# motorcontrol.net
KiCad netlist of a schematic drawn in EAGLE
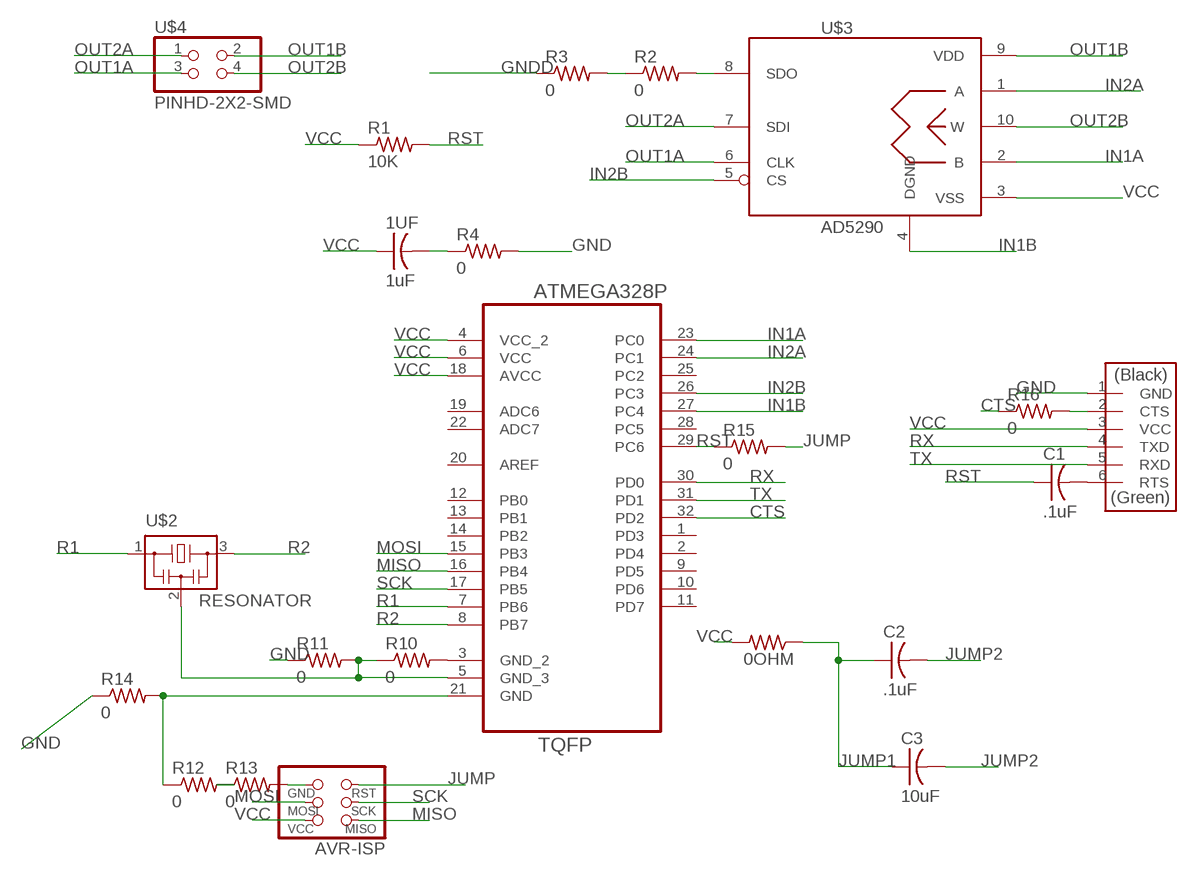
[diagram p0: schematic, sheet 1]

(export (version "E")
  (design (tool "Eeschema 10.0.6"))
  (components
    (comp (ref "0OHM")
      (value "RES-US1206FAB")
      (footprint "eagle-import:R1206FAB")
      (libsource (lib "eagle-import") (part "RES-US1206FAB"))
    )
    (comp (ref "1UF")
      (value "1uF")
      (footprint "eagle-import:C1206FAB")
      (libsource (lib "eagle-import") (part "CAP-US1206FAB"))
    )
    (comp (ref "AVR-ISP")
      (value "AVRISPSMD")
      (footprint "eagle-import:2X03SMD")
      (libsource (lib "eagle-import") (part "AVRISPSMD"))
    )
    (comp (ref "C1")
      (value ".1uF")
      (footprint "eagle-import:C1206FAB")
      (libsource (lib "eagle-import") (part "CAP-US1206FAB"))
    )
    (comp (ref "C2")
      (value ".1uF")
      (footprint "eagle-import:C1206FAB")
      (libsource (lib "eagle-import") (part "CAP-US1206FAB"))
    )
    (comp (ref "C3")
      (value "10uF")
      (footprint "eagle-import:C1206FAB")
      (libsource (lib "eagle-import") (part "CAP-US1206FAB"))
    )
    (comp (ref "R1")
      (value "10K")
      (footprint "eagle-import:R1206FAB")
      (libsource (lib "eagle-import") (part "RES-US1206FAB"))
    )
    (comp (ref "R2")
      (value "0")
      (footprint "eagle-import:R1206FAB")
      (libsource (lib "eagle-import") (part "RES-US1206FAB"))
    )
    (comp (ref "R3")
      (value "0")
      (footprint "eagle-import:R1206FAB")
      (libsource (lib "eagle-import") (part "RES-US1206FAB"))
    )
    (comp (ref "R4")
      (value "0")
      (footprint "eagle-import:R1206FAB")
      (libsource (lib "eagle-import") (part "RES-US1206FAB"))
    )
    (comp (ref "R10")
      (value "0")
      (footprint "eagle-import:R1206FAB")
      (libsource (lib "eagle-import") (part "RES-US1206FAB"))
    )
    (comp (ref "R11")
      (value "0")
      (footprint "eagle-import:R1206FAB")
      (libsource (lib "eagle-import") (part "RES-US1206FAB"))
    )
    (comp (ref "R12")
      (value "0")
      (footprint "eagle-import:R1206")
      (libsource (lib "eagle-import") (part "RES-US1206"))
    )
    (comp (ref "R13")
      (value "0")
      (footprint "eagle-import:R1206")
      (libsource (lib "eagle-import") (part "RES-US1206"))
    )
    (comp (ref "R14")
      (value "0")
      (footprint "eagle-import:R1206FAB")
      (libsource (lib "eagle-import") (part "RES-US1206FAB"))
    )
    (comp (ref "R15")
      (value "0")
      (footprint "eagle-import:R1206FAB")
      (libsource (lib "eagle-import") (part "RES-US1206FAB"))
    )
    (comp (ref "R16")
      (value "0")
      (footprint "eagle-import:R1206FAB")
      (libsource (lib "eagle-import") (part "RES-US1206FAB"))
    )
    (comp (ref "U$1")
      (value "FTDI-SMD-HEADER")
      (footprint "eagle-import:1X06SMD")
      (libsource (lib "eagle-import") (part "FTDI-SMD-HEADER"))
    )
    (comp (ref "U$2")
      (value "RESONATOR")
      (footprint "eagle-import:EFOBM")
      (libsource (lib "eagle-import") (part "RESONATOR"))
    )
    (comp (ref "U$3")
      (value "AD5290")
      (footprint "eagle-import:MSOP_10")
      (libsource (lib "eagle-import") (part "AD5290"))
    )
    (comp (ref "U$4")
      (value "PINHD-2X2-SMD")
      (footprint "eagle-import:2X02SMD")
      (libsource (lib "eagle-import") (part "PINHD-2X2-SMD"))
    )
    (comp (ref "U1")
      (value "ATMEGA328P-AU")
      (footprint "eagle-import:QFP80P900X900X120-32N")
      (libsource (lib "eagle-import") (part "ATMEGA328P-AU"))
    )
  )
  (nets
    (net (code "1") (name "/CTS") (class "Default")
      (node (ref "R16") (pin "1") (pinfunction "1_1") (pintype "passive"))
      (node (ref "U1") (pin "32") (pinfunction "PD2_32") (pintype "bidirectional"))
    )
    (net (code "2") (name "/GND") (class "Default")
      (node (ref "R11") (pin "1") (pinfunction "1_1") (pintype "passive"))
      (node (ref "R14") (pin "1") (pinfunction "1_1") (pintype "passive"))
      (node (ref "R4") (pin "2") (pinfunction "2_2") (pintype "passive"))
      (node (ref "U$1") (pin "1") (pinfunction "GND_1") (pintype "bidirectional"))
    )
    (net (code "3") (name "/GNDD") (class "Default")
      (node (ref "R12") (pin "1") (pinfunction "1_1") (pintype "passive"))
      (node (ref "R14") (pin "2") (pinfunction "2_2") (pintype "passive"))
      (node (ref "R3") (pin "1") (pinfunction "1_1") (pintype "passive"))
      (node (ref "U1") (pin "21") (pinfunction "GND_21") (pintype "passive"))
    )
    (net (code "4") (name "/IN1A") (class "Default")
      (node (ref "U$3") (pin "2") (pinfunction "B_2") (pintype "bidirectional"))
      (node (ref "U1") (pin "23") (pinfunction "PC0_23") (pintype "bidirectional"))
    )
    (net (code "5") (name "/IN1B") (class "Default")
      (node (ref "U$3") (pin "4") (pinfunction "DGND_4") (pintype "bidirectional"))
      (node (ref "U1") (pin "27") (pinfunction "PC4_27") (pintype "bidirectional"))
    )
    (net (code "6") (name "/IN2A") (class "Default")
      (node (ref "U$3") (pin "1") (pinfunction "A_1") (pintype "bidirectional"))
      (node (ref "U1") (pin "24") (pinfunction "PC1_24") (pintype "bidirectional"))
    )
    (net (code "7") (name "/IN2B") (class "Default")
      (node (ref "U$3") (pin "5") (pinfunction "CS_5") (pintype "input"))
      (node (ref "U1") (pin "26") (pinfunction "PC3_26") (pintype "bidirectional"))
    )
    (net (code "8") (name "/JUMP") (class "Default")
      (node (ref "AVR-ISP") (pin "5") (pinfunction "RST_5") (pintype "passive"))
      (node (ref "R15") (pin "2") (pinfunction "2_2") (pintype "passive"))
    )
    (net (code "9") (name "/JUMP1") (class "Default")
      (node (ref "0OHM") (pin "1") (pinfunction "1_1") (pintype "passive"))
      (node (ref "C2") (pin "1") (pinfunction "1_1") (pintype "passive"))
      (node (ref "C3") (pin "1") (pinfunction "1_1") (pintype "passive"))
    )
    (net (code "10") (name "/JUMP2") (class "Default")
      (node (ref "C2") (pin "2") (pinfunction "2_2") (pintype "passive"))
      (node (ref "C3") (pin "2") (pinfunction "2_2") (pintype "passive"))
      (node (ref "R2") (pin "2") (pinfunction "2_2") (pintype "passive"))
      (node (ref "U$3") (pin "8") (pinfunction "SDO_8") (pintype "bidirectional"))
    )
    (net (code "11") (name "/MISO") (class "Default")
      (node (ref "AVR-ISP") (pin "1") (pinfunction "MISO_1") (pintype "passive"))
      (node (ref "U1") (pin "16") (pinfunction "PB4_16") (pintype "bidirectional"))
    )
    (net (code "12") (name "/MOSI") (class "Default")
      (node (ref "AVR-ISP") (pin "4") (pinfunction "MOSI_4") (pintype "passive"))
      (node (ref "U1") (pin "15") (pinfunction "PB3_15") (pintype "bidirectional"))
    )
    (net (code "13") (name "/OUT1A") (class "Default")
      (node (ref "U$3") (pin "6") (pinfunction "CLK_6") (pintype "bidirectional"))
      (node (ref "U$4") (pin "3") (pinfunction "3_3") (pintype "passive"))
    )
    (net (code "14") (name "/OUT1B") (class "Default")
      (node (ref "U$3") (pin "9") (pinfunction "VDD_9") (pintype "bidirectional"))
      (node (ref "U$4") (pin "2") (pinfunction "2_2") (pintype "passive"))
    )
    (net (code "15") (name "/OUT2A") (class "Default")
      (node (ref "U$3") (pin "7") (pinfunction "SDI_7") (pintype "bidirectional"))
      (node (ref "U$4") (pin "1") (pinfunction "1_1") (pintype "passive"))
    )
    (net (code "16") (name "/OUT2B") (class "Default")
      (node (ref "U$3") (pin "10") (pinfunction "W_10") (pintype "bidirectional"))
      (node (ref "U$4") (pin "4") (pinfunction "4_4") (pintype "passive"))
    )
    (net (code "17") (name "/R1") (class "Default")
      (node (ref "U$2") (pin "1") (pinfunction "1_1") (pintype "passive"))
      (node (ref "U1") (pin "7") (pinfunction "PB6_7") (pintype "bidirectional"))
    )
    (net (code "18") (name "/R2") (class "Default")
      (node (ref "U$2") (pin "3") (pinfunction "3_3") (pintype "passive"))
      (node (ref "U1") (pin "8") (pinfunction "PB7_8") (pintype "bidirectional"))
    )
    (net (code "19") (name "/RST") (class "Default")
      (node (ref "C1") (pin "1") (pinfunction "1_1") (pintype "passive"))
      (node (ref "R1") (pin "2") (pinfunction "2_2") (pintype "passive"))
      (node (ref "R15") (pin "1") (pinfunction "1_1") (pintype "passive"))
      (node (ref "U1") (pin "29") (pinfunction "PC6_29") (pintype "bidirectional"))
    )
    (net (code "20") (name "/RX") (class "Default")
      (node (ref "U$1") (pin "4") (pinfunction "TXD_4") (pintype "bidirectional"))
      (node (ref "U1") (pin "30") (pinfunction "PD0_30") (pintype "bidirectional"))
    )
    (net (code "21") (name "/SCK") (class "Default")
      (node (ref "AVR-ISP") (pin "3") (pinfunction "SCK_3") (pintype "passive"))
      (node (ref "U1") (pin "17") (pinfunction "PB5_17") (pintype "bidirectional"))
    )
    (net (code "22") (name "/TX") (class "Default")
      (node (ref "U$1") (pin "5") (pinfunction "RXD_5") (pintype "bidirectional"))
      (node (ref "U1") (pin "31") (pinfunction "PD1_31") (pintype "bidirectional"))
    )
    (net (code "23") (name "/VCC") (class "Default")
      (node (ref "0OHM") (pin "2") (pinfunction "2_2") (pintype "passive"))
      (node (ref "1UF") (pin "1") (pinfunction "1_1") (pintype "passive"))
      (node (ref "AVR-ISP") (pin "2") (pinfunction "VCC_2") (pintype "passive"))
      (node (ref "R1") (pin "1") (pinfunction "1_1") (pintype "passive"))
      (node (ref "U$1") (pin "3") (pinfunction "VCC_3") (pintype "bidirectional"))
      (node (ref "U$3") (pin "3") (pinfunction "VSS_3") (pintype "bidirectional"))
      (node (ref "U1") (pin "18") (pinfunction "AVCC_18") (pintype "power_in"))
      (node (ref "U1") (pin "4") (pinfunction "VCC_2_4") (pintype "power_in"))
      (node (ref "U1") (pin "6") (pinfunction "VCC_6") (pintype "power_in"))
    )
    (net (code "24") (name "Net-(1UF-Pad2)") (class "Default")
      (node (ref "1UF") (pin "2") (pinfunction "2_2") (pintype "passive"))
      (node (ref "R4") (pin "1") (pinfunction "1_1") (pintype "passive"))
    )
    (net (code "25") (name "Net-(AVR-ISP-GND)") (class "Default")
      (node (ref "AVR-ISP") (pin "6") (pinfunction "GND_6") (pintype "passive"))
      (node (ref "R13") (pin "2") (pinfunction "2_2") (pintype "passive"))
    )
    (net (code "26") (name "Net-(R2-Pad1)") (class "Default")
      (node (ref "R2") (pin "1") (pinfunction "1_1") (pintype "passive"))
      (node (ref "R3") (pin "2") (pinfunction "2_2") (pintype "passive"))
    )
    (net (code "27") (name "Net-(R12-Pad2)") (class "Default")
      (node (ref "R12") (pin "2") (pinfunction "2_2") (pintype "passive"))
      (node (ref "R13") (pin "1") (pinfunction "1_1") (pintype "passive"))
    )
    (net (code "28") (name "Net-(U$1-CTS)") (class "Default")
      (node (ref "R16") (pin "2") (pinfunction "2_2") (pintype "passive"))
      (node (ref "U$1") (pin "2") (pinfunction "CTS_2") (pintype "bidirectional"))
    )
    (net (code "29") (name "Net-(U$1-RTS)") (class "Default")
      (node (ref "C1") (pin "2") (pinfunction "2_2") (pintype "passive"))
      (node (ref "U$1") (pin "6") (pinfunction "RTS_6") (pintype "bidirectional"))
    )
    (net (code "30") (name "Net-(U1-GND_2)") (class "Default")
      (node (ref "R10") (pin "2") (pinfunction "2_2") (pintype "passive"))
      (node (ref "U1") (pin "3") (pinfunction "GND_2_3") (pintype "passive"))
    )
    (net (code "31") (name "Net-(U1-GND_3)") (class "Default")
      (node (ref "R10") (pin "1") (pinfunction "1_1") (pintype "passive"))
      (node (ref "R11") (pin "2") (pinfunction "2_2") (pintype "passive"))
      (node (ref "U$2") (pin "2") (pinfunction "2_2") (pintype "passive"))
      (node (ref "U1") (pin "5") (pinfunction "GND_3_5") (pintype "passive"))
    )
    (net (code "32") (name "unconnected-(U1-ADC6-Pad19)") (class "Default")
      (node (ref "U1") (pin "19") (pinfunction "ADC6_19") (pintype "input"))
    )
    (net (code "33") (name "unconnected-(U1-ADC7-Pad22)") (class "Default")
      (node (ref "U1") (pin "22") (pinfunction "ADC7_22") (pintype "input"))
    )
    (net (code "34") (name "unconnected-(U1-AREF-Pad20)") (class "Default")
      (node (ref "U1") (pin "20") (pinfunction "AREF_20") (pintype "input"))
    )
    (net (code "35") (name "unconnected-(U1-PB0-Pad12)") (class "Default")
      (node (ref "U1") (pin "12") (pinfunction "PB0_12") (pintype "bidirectional"))
    )
    (net (code "36") (name "unconnected-(U1-PB1-Pad13)") (class "Default")
      (node (ref "U1") (pin "13") (pinfunction "PB1_13") (pintype "bidirectional"))
    )
    (net (code "37") (name "unconnected-(U1-PB2-Pad14)") (class "Default")
      (node (ref "U1") (pin "14") (pinfunction "PB2_14") (pintype "bidirectional"))
    )
    (net (code "38") (name "unconnected-(U1-PC2-Pad25)") (class "Default")
      (node (ref "U1") (pin "25") (pinfunction "PC2_25") (pintype "bidirectional"))
    )
    (net (code "39") (name "unconnected-(U1-PC5-Pad28)") (class "Default")
      (node (ref "U1") (pin "28") (pinfunction "PC5_28") (pintype "bidirectional"))
    )
    (net (code "40") (name "unconnected-(U1-PD3-Pad1)") (class "Default")
      (node (ref "U1") (pin "1") (pinfunction "PD3_1") (pintype "bidirectional"))
    )
    (net (code "41") (name "unconnected-(U1-PD4-Pad2)") (class "Default")
      (node (ref "U1") (pin "2") (pinfunction "PD4_2") (pintype "bidirectional"))
    )
    (net (code "42") (name "unconnected-(U1-PD5-Pad9)") (class "Default")
      (node (ref "U1") (pin "9") (pinfunction "PD5_9") (pintype "bidirectional"))
    )
    (net (code "43") (name "unconnected-(U1-PD6-Pad10)") (class "Default")
      (node (ref "U1") (pin "10") (pinfunction "PD6_10") (pintype "bidirectional"))
    )
    (net (code "44") (name "unconnected-(U1-PD7-Pad11)") (class "Default")
      (node (ref "U1") (pin "11") (pinfunction "PD7_11") (pintype "bidirectional"))
    )
  )
)
